# PCB_Toto.net
KiCad netlist of a schematic drawn in Altium Designer
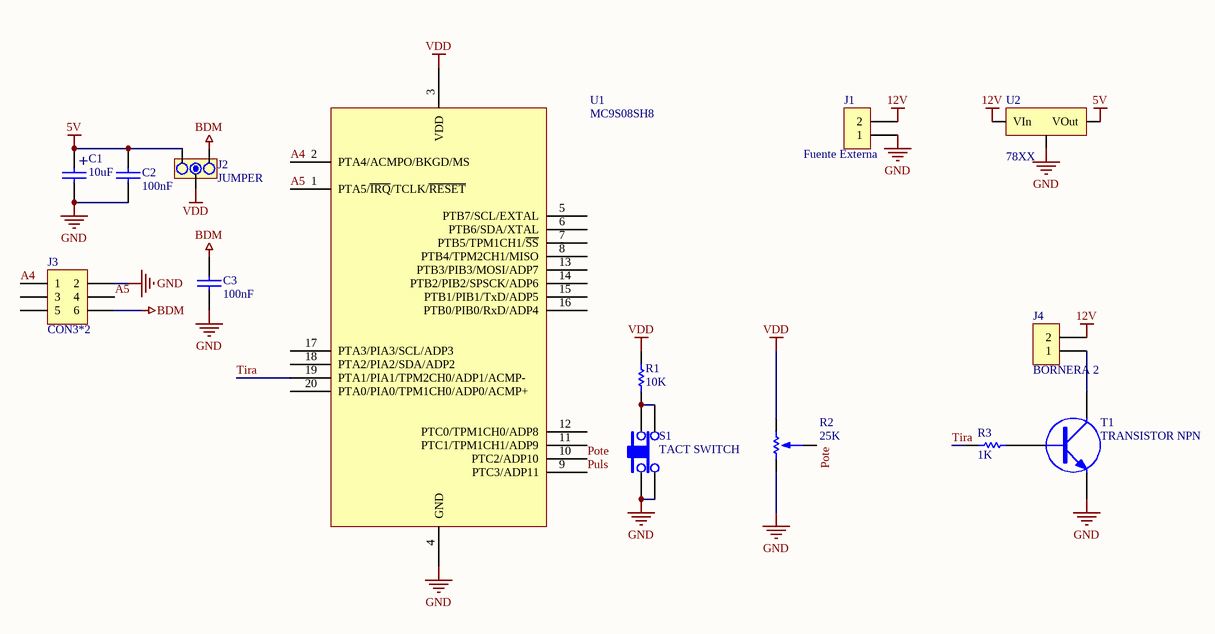
[diagram p0: PCB_Toto.SchDoc]

(export (version "E")
  (design (tool "Eeschema 10.0.6"))
  (components
    (comp (ref "C1") (value "10uF") (footprint "CAP100RP") (libsource (lib "My_Library") (part "CAPPOL")))
    (comp (ref "C2") (value "100nF") (footprint "0805") (libsource (lib "My_Library") (part "CAP")))
    (comp (ref "C3") (value "100nF") (footprint "0805") (libsource (lib "My_Library") (part "CAP")))
    (comp (ref "J1")
      (value "Fuente Externa")
      (footprint "BORNERA2")
      (libsource (lib "My_Library") (part "BORNERA 2"))
    )
    (comp (ref "J2") (value "JUMPER") (footprint "JUMPER3") (libsource (lib "My_Library") (part "JUMPER3")))
    (comp (ref "J3") (value "CON3*2") (footprint "SIP3*2") (libsource (lib "My_Library") (part "PIN3*2")))
    (comp (ref "J4")
      (value "BORNERA 2")
      (footprint "BORNERA2")
      (libsource (lib "My_Library") (part "BORNERA 2"))
    )
    (comp (ref "R1") (value "10K") (footprint "0805") (libsource (lib "My_Library") (part "RES")))
    (comp (ref "R2")
      (value "25K")
      (footprint "POTENCIOMETRO")
      (libsource (lib "My_Library") (part "POTENCIOMETRO"))
    )
    (comp (ref "R3") (value "1K") (footprint "RES400") (libsource (lib "My_Library") (part "RES")))
    (comp (ref "S1")
      (value "TACT SWITCH")
      (footprint "TACTSWITCH")
      (libsource (lib "My_Library") (part "TACT SWITCH"))
    )
    (comp (ref "T1")
      (value "TRANSISTOR NPN")
      (footprint "TO-220 V")
      (libsource (lib "My_Library") (part "TRANSISTOR NPN"))
    )
    (comp (ref "U1")
      (value "MC9S08SH8")
      (footprint "DIP20")
      (description "IC MCU 8BIT 8K FLASH 20-DIP")
      (libsource (lib "My_Library") (part "MC9S08SH8"))
    )
    (comp (ref "U2")
      (value "78XX")
      (footprint "DPAK")
      (description "REGULDOR POSITIVO")
      (libsource (lib "My_Library") (part "78XX"))
    )
  )
  (nets
    (net (code "1") (name "/A4") (class "Default")
      (node (ref "J3") (pin "1") (pinfunction "1_1") (pintype "passive"))
      (node (ref "U1") (pin "2") (pinfunction "PTA4/ACMPO/BKGD/MS_2") (pintype "passive"))
    )
    (net (code "2") (name "/A5") (class "Default")
      (node (ref "J3") (pin "4") (pinfunction "4_4") (pintype "passive"))
      (node (ref "U1") (pin "1") (pinfunction "PTA5/~{IRQ}/TCLK/~{RESET}_1") (pintype "passive"))
    )
    (net (code "3") (name "/Pote") (class "Default")
      (node (ref "R2") (pin "2") (pinfunction "2_2") (pintype "passive"))
      (node (ref "U1") (pin "10") (pinfunction "PTC2/ADP10_10") (pintype "passive"))
    )
    (net (code "4") (name "/Puls") (class "Default")
      (node (ref "U1") (pin "9") (pinfunction "PTC3/ADP11_9") (pintype "passive"))
    )
    (net (code "5") (name "/Tira") (class "Default")
      (node (ref "R3") (pin "1") (pinfunction "1_1") (pintype "passive"))
      (node (ref "U1") (pin "19") (pinfunction "PTA1/PIA1/TPM2CH0/ADP1/ACMP-_19") (pintype "passive"))
    )
    (net (code "6") (name "5V") (class "Default")
      (node (ref "C1") (pin "1") (pinfunction "1_1") (pintype "passive"))
      (node (ref "C2") (pin "1") (pinfunction "1_1") (pintype "passive"))
      (node (ref "J2") (pin "1") (pinfunction "1_1") (pintype "passive"))
      (node (ref "U2") (pin "3") (pinfunction "VOut_3") (pintype "passive"))
    )
    (net (code "7") (name "12V") (class "Default")
      (node (ref "J1") (pin "2") (pinfunction "2_2") (pintype "passive"))
      (node (ref "J4") (pin "2") (pinfunction "2_2") (pintype "passive"))
      (node (ref "U2") (pin "1") (pinfunction "VIn_1") (pintype "passive"))
    )
    (net (code "8") (name "BDM") (class "Default")
      (node (ref "C3") (pin "1") (pinfunction "1_1") (pintype "passive"))
      (node (ref "J2") (pin "3") (pinfunction "3_3") (pintype "passive"))
      (node (ref "J3") (pin "6") (pinfunction "6_6") (pintype "passive"))
    )
    (net (code "9") (name "GND") (class "Default")
      (node (ref "C1") (pin "2") (pinfunction "2_2") (pintype "passive"))
      (node (ref "C2") (pin "2") (pinfunction "2_2") (pintype "passive"))
      (node (ref "C3") (pin "2") (pinfunction "2_2") (pintype "passive"))
      (node (ref "J1") (pin "1") (pinfunction "1_1") (pintype "passive"))
      (node (ref "J3") (pin "2") (pinfunction "2_2") (pintype "passive"))
      (node (ref "R2") (pin "3") (pinfunction "3_3") (pintype "passive"))
      (node (ref "S1") (pin "1") (pinfunction "1_1") (pintype "passive"))
      (node (ref "S1") (pin "2") (pinfunction "2_2") (pintype "passive"))
      (node (ref "T1") (pin "3") (pinfunction "E_3") (pintype "passive"))
      (node (ref "U1") (pin "4") (pinfunction "GND_4") (pintype "passive"))
      (node (ref "U2") (pin "2") (pinfunction "GND_2") (pintype "passive"))
    )
    (net (code "10") (name "Net-(R1-Pad1)") (class "Default")
      (node (ref "R1") (pin "1") (pinfunction "1_1") (pintype "passive"))
      (node (ref "S1") (pin "3") (pinfunction "3_3") (pintype "passive"))
      (node (ref "S1") (pin "4") (pinfunction "4_4") (pintype "passive"))
    )
    (net (code "11") (name "Net-(T1-B)") (class "Default")
      (node (ref "R3") (pin "2") (pinfunction "2_2") (pintype "passive"))
      (node (ref "T1") (pin "1") (pinfunction "B_1") (pintype "passive"))
    )
    (net (code "12") (name "Net-(T1-C)") (class "Default")
      (node (ref "J4") (pin "1") (pinfunction "1_1") (pintype "passive"))
      (node (ref "T1") (pin "2") (pinfunction "C_2") (pintype "passive"))
    )
    (net (code "13") (name "VDD") (class "Default")
      (node (ref "J2") (pin "2") (pinfunction "2_2") (pintype "passive"))
      (node (ref "R1") (pin "2") (pinfunction "2_2") (pintype "passive"))
      (node (ref "R2") (pin "1") (pinfunction "1_1") (pintype "passive"))
      (node (ref "U1") (pin "3") (pinfunction "VDD_3") (pintype "passive"))
    )
    (net (code "14") (name "unconnected-(J3-Pad3)") (class "Default")
      (node (ref "J3") (pin "3") (pinfunction "3_3") (pintype "passive"))
    )
    (net (code "15") (name "unconnected-(J3-Pad5)") (class "Default")
      (node (ref "J3") (pin "5") (pinfunction "5_5") (pintype "passive"))
    )
    (net (code "16") (name "unconnected-(U1-PTA0{slash}PIA0{slash}TPM1CH0{slash}ADP0{slash}ACMP+-Pad20)") (class "Default")
      (node (ref "U1") (pin "20") (pinfunction "PTA0/PIA0/TPM1CH0/ADP0/ACMP+_20") (pintype "passive"))
    )
    (net (code "17") (name "unconnected-(U1-PTA2{slash}PIA2{slash}SDA{slash}ADP2-Pad18)") (class "Default")
      (node (ref "U1") (pin "18") (pinfunction "PTA2/PIA2/SDA/ADP2_18") (pintype "passive"))
    )
    (net (code "18") (name "unconnected-(U1-PTA3{slash}PIA3{slash}SCL{slash}ADP3-Pad17)") (class "Default")
      (node (ref "U1") (pin "17") (pinfunction "PTA3/PIA3/SCL/ADP3_17") (pintype "passive"))
    )
    (net (code "19") (name "unconnected-(U1-PTB0{slash}PIB0{slash}RxD{slash}ADP4-Pad16)") (class "Default")
      (node (ref "U1") (pin "16") (pinfunction "PTB0/PIB0/RxD/ADP4_16") (pintype "passive"))
    )
    (net (code "20") (name "unconnected-(U1-PTB1{slash}PIB1{slash}TxD{slash}ADP5-Pad15)") (class "Default")
      (node (ref "U1") (pin "15") (pinfunction "PTB1/PIB1/TxD/ADP5_15") (pintype "passive"))
    )
    (net (code "21") (name "unconnected-(U1-PTB2{slash}PIB2{slash}SPSCK{slash}ADP6-Pad14)") (class "Default")
      (node (ref "U1") (pin "14") (pinfunction "PTB2/PIB2/SPSCK/ADP6_14") (pintype "passive"))
    )
    (net (code "22") (name "unconnected-(U1-PTB3{slash}PIB3{slash}MOSI{slash}ADP7-Pad13)") (class "Default")
      (node (ref "U1") (pin "13") (pinfunction "PTB3/PIB3/MOSI/ADP7_13") (pintype "passive"))
    )
    (net (code "23") (name "unconnected-(U1-PTB4{slash}TPM2CH1{slash}MISO-Pad8)") (class "Default")
      (node (ref "U1") (pin "8") (pinfunction "PTB4/TPM2CH1/MISO_8") (pintype "passive"))
    )
    (net (code "24") (name "unconnected-(U1-PTB5{slash}TPM1CH1{slash}~{SS}-Pad7)") (class "Default")
      (node (ref "U1") (pin "7") (pinfunction "PTB5/TPM1CH1/~{SS}_7") (pintype "passive"))
    )
    (net (code "25") (name "unconnected-(U1-PTB6{slash}SDA{slash}XTAL-Pad6)") (class "Default")
      (node (ref "U1") (pin "6") (pinfunction "PTB6/SDA/XTAL_6") (pintype "passive"))
    )
    (net (code "26") (name "unconnected-(U1-PTB7{slash}SCL{slash}EXTAL-Pad5)") (class "Default")
      (node (ref "U1") (pin "5") (pinfunction "PTB7/SCL/EXTAL_5") (pintype "passive"))
    )
    (net (code "27") (name "unconnected-(U1-PTC0{slash}TPM1CH0{slash}ADP8-Pad12)") (class "Default")
      (node (ref "U1") (pin "12") (pinfunction "PTC0/TPM1CH0/ADP8_12") (pintype "passive"))
    )
    (net (code "28") (name "unconnected-(U1-PTC1{slash}TPM1CH1{slash}ADP9-Pad11)") (class "Default")
      (node (ref "U1") (pin "11") (pinfunction "PTC1/TPM1CH1/ADP9_11") (pintype "passive"))
    )
  )
)
